# Microcontroller_block.net
KiCad netlist of a schematic drawn in Altium Designer
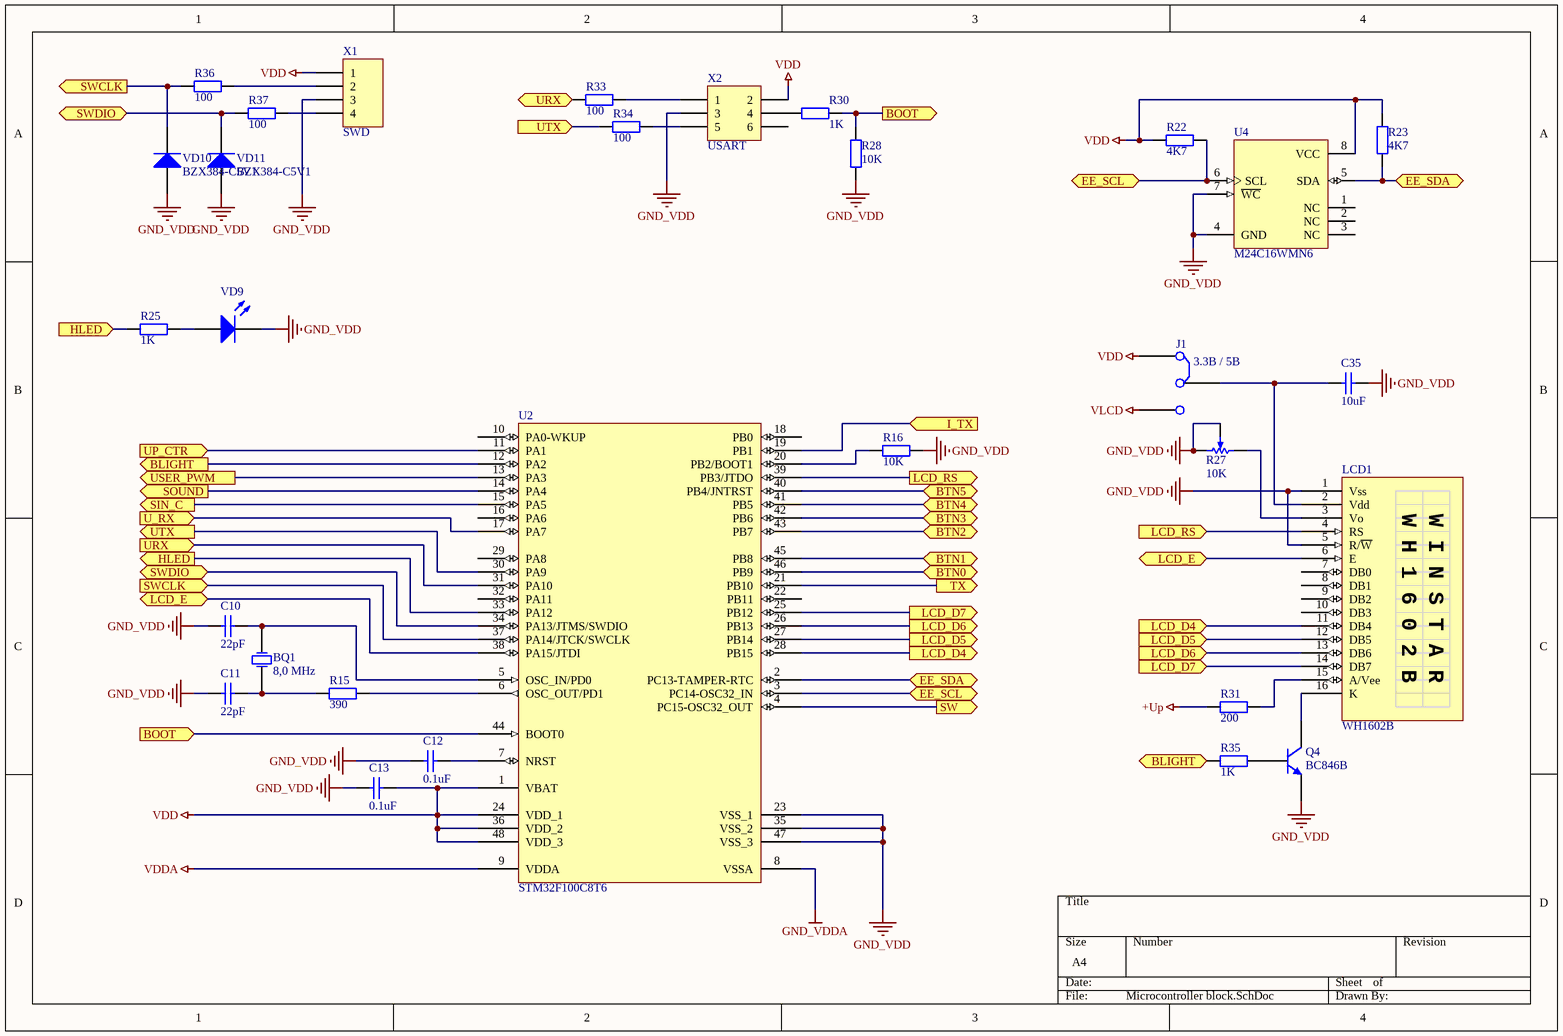
[diagram p0: Microcontroller block.SchDoc]

(export (version "E")
  (design (tool "Eeschema 10.0.6"))
  (components
    (comp (ref "BQ1")
      (value "8,0 MHz")
      (footprint "HC-49/U3H (low profile)")
      (description "Crystal Oscillator")
      (fields (field (name "PUBLISHER") "Altium Limited"))
      (libsource (lib "Quasar ARM") (part "XTAL"))
    )
    (comp (ref "C10")
      (value "22pF")
      (footprint "0805")
      (description "Capacitor")
      (fields (field (name "PUBLISHER") "Altium Limited"))
      (libsource (lib "Quasar ARM") (part "Capacitor SMD"))
    )
    (comp (ref "C11")
      (value "22pF")
      (footprint "0805")
      (description "Capacitor")
      (fields (field (name "PUBLISHER") "Altium Limited"))
      (libsource (lib "Quasar ARM") (part "Capacitor SMD"))
    )
    (comp (ref "C12")
      (value "0.1uF")
      (footprint "0805")
      (description "Capacitor")
      (fields (field (name "PUBLISHER") "Altium Limited"))
      (libsource (lib "Quasar ARM") (part "Capacitor SMD"))
    )
    (comp (ref "C13")
      (value "0.1uF")
      (footprint "1206_SMD_Capacitor")
      (description "Capacitor")
      (fields (field (name "PUBLISHER") "Altium Limited"))
      (libsource (lib "Quasar ARM") (part "Capacitor SMD"))
    )
    (comp (ref "C35")
      (value "10uF")
      (footprint "1206_SMD_Capacitor")
      (description "Capacitor")
      (fields (field (name "PUBLISHER") "Altium Limited"))
      (libsource (lib "Quasar ARM") (part "Capacitor SMD"))
    )
    (comp (ref "J1")
      (value "3.3В / 5В")
      (footprint "1206_SMD_JUMPER SELECTOR")
      (libsource (lib "Quasar ARM") (part "Jump Selector"))
    )
    (comp (ref "LCD1")
      (value "WH1602B")
      (footprint "WS1602B-3")
      (description "Символьный ЖКИ разрешением 16 символов на 2 строки")
      (libsource (lib "Quasar ARM") (part "WH1602B"))
    )
    (comp (ref "Q4")
      (value "BC846B")
      (footprint "SOT23_N")
      (description "NPN General-purpose Transistor")
      (fields (field (name "PUBLISHER") "Altium Limited"))
      (libsource (lib "Quasar ARM") (part "BC846B"))
    )
    (comp (ref "R15")
      (value "390")
      (footprint "1206_SMD_Resistor")
      (description "Resistor")
      (fields (field (name "PUBLISHER") "Altium Limited"))
      (libsource (lib "Quasar ARM") (part "Resistor"))
    )
    (comp (ref "R16")
      (value "10K")
      (footprint "1206_SMD_Resistor")
      (description "Resistor")
      (fields (field (name "PUBLISHER") "Altium Limited"))
      (libsource (lib "Quasar ARM") (part "Resistor"))
    )
    (comp (ref "R22")
      (value "4K7")
      (footprint "1206_SMD_Resistor")
      (description "Resistor")
      (fields (field (name "PUBLISHER") "Altium Limited"))
      (libsource (lib "Quasar ARM") (part "Resistor"))
    )
    (comp (ref "R23")
      (value "4K7")
      (footprint "1206_SMD_Resistor")
      (description "Resistor")
      (fields (field (name "PUBLISHER") "Altium Limited"))
      (libsource (lib "") (part "Resistor_1"))
    )
    (comp (ref "R25")
      (value "1K")
      (footprint "1206_SMD_Resistor")
      (description "Resistor")
      (fields (field (name "PUBLISHER") "Altium Limited"))
      (libsource (lib "") (part "Resistor_2"))
    )
    (comp (ref "R27")
      (value "10K")
      (footprint "3362P")
      (description "Square Trimming Potentiometer")
      (fields (field (name "PUBLISHER") "Altium Limited"))
      (libsource (lib "Quasar ARM") (part "Trimming Potentiometer"))
    )
    (comp (ref "R28")
      (value "10K")
      (footprint "1206_SMD_Resistor")
      (description "Resistor")
      (fields (field (name "PUBLISHER") "Altium Limited"))
      (libsource (lib "") (part "Resistor_1"))
    )
    (comp (ref "R30")
      (value "1K")
      (footprint "1206_SMD_Resistor")
      (description "Resistor")
      (fields (field (name "PUBLISHER") "Altium Limited"))
      (libsource (lib "Quasar ARM") (part "Resistor"))
    )
    (comp (ref "R31")
      (value "200")
      (footprint "1206_SMD_Resistor")
      (description "Resistor")
      (fields (field (name "PUBLISHER") "Altium Limited"))
      (libsource (lib "Quasar ARM") (part "Resistor"))
    )
    (comp (ref "R33")
      (value "100")
      (footprint "1206_SMD_Resistor")
      (description "Resistor")
      (fields (field (name "PUBLISHER") "Altium Limited"))
      (libsource (lib "Quasar ARM") (part "Resistor"))
    )
    (comp (ref "R34")
      (value "100")
      (footprint "1206_SMD_Resistor")
      (description "Resistor")
      (fields (field (name "PUBLISHER") "Altium Limited"))
      (libsource (lib "Quasar ARM") (part "Resistor"))
    )
    (comp (ref "R35")
      (value "1K")
      (footprint "1206_SMD_Resistor")
      (description "Resistor")
      (fields (field (name "PUBLISHER") "Altium Limited"))
      (libsource (lib "Quasar ARM") (part "Resistor"))
    )
    (comp (ref "R36")
      (value "100")
      (footprint "1206_SMD_Resistor")
      (description "Resistor")
      (fields (field (name "PUBLISHER") "Altium Limited"))
      (libsource (lib "Quasar ARM") (part "Resistor"))
    )
    (comp (ref "R37")
      (value "100")
      (footprint "1206_SMD_Resistor")
      (description "Resistor")
      (fields (field (name "PUBLISHER") "Altium Limited"))
      (libsource (lib "Quasar ARM") (part "Resistor"))
    )
    (comp (ref "U2")
      (value "STM32F100C8T6")
      (footprint "LQFP-48_L")
      (description "STM32 ARM-based 32-bit MCU with 64 Kbytes Flash, 48-pin LQFP, Industrial Temperature")
      (fields (field (name "PUBLISHER") "Altium Limited"))
      (libsource (lib "Quasar ARM") (part "STM32F101C8T6"))
    )
    (comp (ref "U4")
      (value "M24C16WMN6")
      (footprint "SO-8")
      (description "16Kbit Serial IІC Bus EEPROM")
      (fields (field (name "PUBLISHER") "Altium Limited"))
      (libsource (lib "Quasar ARM") (part "M24C16WMN6"))
    )
    (comp (ref "VD9")
      (value "LED0")
      (footprint "1206_SMD_Resistor")
      (description "Typical INFRARED GaAs LED")
      (fields (field (name "PUBLISHER") "Altium Limited"))
      (libsource (lib "Quasar ARM") (part "LED0"))
    )
    (comp (ref "VD10")
      (value "BZX384-C5V1")
      (footprint "SOD323")
      (description "Voltage Regulator Diode")
      (fields (field (name "PUBLISHER") "Altium Limited"))
      (libsource (lib "Quasar ARM") (part "BZX84-C5V1"))
    )
    (comp (ref "VD11")
      (value "BZX384-C5V1")
      (footprint "SOD323")
      (description "Voltage Regulator Diode")
      (fields (field (name "PUBLISHER") "Altium Limited"))
      (libsource (lib "Quasar ARM") (part "BZX84-C5V1"))
    )
    (comp (ref "X1")
      (value "SWD")
      (footprint "HDR1X4")
      (description "Header, 4-Pin")
      (fields (field (name "PUBLISHER") "Altium Limited"))
      (libsource (lib "Miscellaneous Connectors") (part "Header 4"))
    )
    (comp (ref "X2")
      (value "USART")
      (footprint "HDR2X3")
      (description "Header, 3-Pin, Dual row")
      (fields (field (name "PUBLISHER") "Altium Limited"))
      (libsource (lib "Miscellaneous Connectors") (part "Header 3X2"))
    )
  )
  (nets
    (net (code "1") (name "+Up") (class "Default")
      (node (ref "R31") (pin "1") (pinfunction "1_1") (pintype "passive"))
    )
    (net (code "2") (name "/BLIGHT") (class "Default")
      (node (ref "R35") (pin "1") (pinfunction "1_1") (pintype "passive"))
      (node (ref "U2") (pin "12") (pinfunction "PA2_12") (pintype "bidirectional"))
    )
    (net (code "3") (name "/BOOT") (class "Default")
      (node (ref "R28") (pin "2") (pinfunction "2_2") (pintype "passive"))
      (node (ref "R30") (pin "2") (pinfunction "2_2") (pintype "passive"))
      (node (ref "U2") (pin "44") (pinfunction "BOOT0_44") (pintype "input"))
    )
    (net (code "4") (name "/BTN0") (class "Default")
      (node (ref "U2") (pin "46") (pinfunction "PB9_46") (pintype "bidirectional"))
    )
    (net (code "5") (name "/BTN1") (class "Default")
      (node (ref "U2") (pin "45") (pinfunction "PB8_45") (pintype "bidirectional"))
    )
    (net (code "6") (name "/BTN2") (class "Default")
      (node (ref "U2") (pin "43") (pinfunction "PB7_43") (pintype "bidirectional"))
    )
    (net (code "7") (name "/BTN3") (class "Default")
      (node (ref "U2") (pin "42") (pinfunction "PB6_42") (pintype "bidirectional"))
    )
    (net (code "8") (name "/BTN4") (class "Default")
      (node (ref "U2") (pin "41") (pinfunction "PB5_41") (pintype "bidirectional"))
    )
    (net (code "9") (name "/BTN5") (class "Default")
      (node (ref "U2") (pin "40") (pinfunction "PB4/JNTRST_40") (pintype "bidirectional"))
    )
    (net (code "10") (name "/EE_SCL") (class "Default")
      (node (ref "R22") (pin "2") (pinfunction "2_2") (pintype "passive"))
      (node (ref "U2") (pin "3") (pinfunction "PC14-OSC32_IN_3") (pintype "bidirectional"))
      (node (ref "U4") (pin "6") (pinfunction "SCL_6") (pintype "input"))
    )
    (net (code "11") (name "/EE_SDA") (class "Default")
      (node (ref "R23") (pin "1") (pinfunction "1_1") (pintype "passive"))
      (node (ref "U2") (pin "2") (pinfunction "PC13-TAMPER-RTC_2") (pintype "bidirectional"))
      (node (ref "U4") (pin "5") (pinfunction "SDA_5") (pintype "bidirectional"))
    )
    (net (code "12") (name "/HLED") (class "Default")
      (node (ref "R25") (pin "2") (pinfunction "2_2") (pintype "passive"))
      (node (ref "U2") (pin "33") (pinfunction "PA12_33") (pintype "bidirectional"))
    )
    (net (code "13") (name "/I_TX") (class "Default")
      (node (ref "U2") (pin "19") (pinfunction "PB1_19") (pintype "bidirectional"))
    )
    (net (code "14") (name "/LCD_D4") (class "Default")
      (node (ref "LCD1") (pin "11") (pinfunction "DB4_11") (pintype "bidirectional"))
      (node (ref "U2") (pin "28") (pinfunction "PB15_28") (pintype "bidirectional"))
    )
    (net (code "15") (name "/LCD_D5") (class "Default")
      (node (ref "LCD1") (pin "12") (pinfunction "DB5_12") (pintype "bidirectional"))
      (node (ref "U2") (pin "27") (pinfunction "PB14_27") (pintype "bidirectional"))
    )
    (net (code "16") (name "/LCD_D6") (class "Default")
      (node (ref "LCD1") (pin "13") (pinfunction "DB6_13") (pintype "bidirectional"))
      (node (ref "U2") (pin "26") (pinfunction "PB13_26") (pintype "bidirectional"))
    )
    (net (code "17") (name "/LCD_D7") (class "Default")
      (node (ref "LCD1") (pin "14") (pinfunction "DB7_14") (pintype "bidirectional"))
      (node (ref "U2") (pin "25") (pinfunction "PB12_25") (pintype "bidirectional"))
    )
    (net (code "18") (name "/LCD_E") (class "Default")
      (node (ref "LCD1") (pin "6") (pinfunction "E_6") (pintype "input"))
      (node (ref "U2") (pin "38") (pinfunction "PA15/JTDI_38") (pintype "bidirectional"))
    )
    (net (code "19") (name "/LCD_RS") (class "Default")
      (node (ref "LCD1") (pin "4") (pinfunction "RS_4") (pintype "input"))
      (node (ref "U2") (pin "39") (pinfunction "PB3/JTDO_39") (pintype "bidirectional"))
    )
    (net (code "20") (name "/SIN_C") (class "Default")
      (node (ref "U2") (pin "15") (pinfunction "PA5_15") (pintype "bidirectional"))
    )
    (net (code "21") (name "/SOUND") (class "Default")
      (node (ref "U2") (pin "14") (pinfunction "PA4_14") (pintype "bidirectional"))
    )
    (net (code "22") (name "/SW") (class "Default")
      (node (ref "U2") (pin "4") (pinfunction "PC15-OSC32_OUT_4") (pintype "bidirectional"))
    )
    (net (code "23") (name "/SWCLK") (class "Default")
      (node (ref "R36") (pin "1") (pinfunction "1_1") (pintype "passive"))
      (node (ref "U2") (pin "37") (pinfunction "PA14/JTCK/SWCLK_37") (pintype "bidirectional"))
      (node (ref "VD10") (pin "3") (pinfunction "K_3") (pintype "passive"))
    )
    (net (code "24") (name "/SWDIO") (class "Default")
      (node (ref "R37") (pin "1") (pinfunction "1_1") (pintype "passive"))
      (node (ref "U2") (pin "34") (pinfunction "PA13/JTMS/SWDIO_34") (pintype "bidirectional"))
      (node (ref "VD11") (pin "3") (pinfunction "K_3") (pintype "passive"))
    )
    (net (code "25") (name "/TX") (class "Default")
      (node (ref "U2") (pin "21") (pinfunction "PB10_21") (pintype "bidirectional"))
    )
    (net (code "26") (name "/UP_CTR") (class "Default")
      (node (ref "U2") (pin "11") (pinfunction "PA1_11") (pintype "bidirectional"))
    )
    (net (code "27") (name "/URX") (class "Default")
      (node (ref "R33") (pin "1") (pinfunction "1_1") (pintype "passive"))
      (node (ref "U2") (pin "31") (pinfunction "PA10_31") (pintype "bidirectional"))
    )
    (net (code "28") (name "/USER_PWM") (class "Default")
      (node (ref "U2") (pin "13") (pinfunction "PA3_13") (pintype "bidirectional"))
    )
    (net (code "29") (name "/UTX") (class "Default")
      (node (ref "R34") (pin "1") (pinfunction "1_1") (pintype "passive"))
      (node (ref "U2") (pin "30") (pinfunction "PA9_30") (pintype "bidirectional"))
    )
    (net (code "30") (name "/U_RX") (class "Default")
      (node (ref "U2") (pin "17") (pinfunction "PA7_17") (pintype "bidirectional"))
    )
    (net (code "31") (name "GND_VDD") (class "Default")
      (node (ref "C10") (pin "1") (pinfunction "1_1") (pintype "passive"))
      (node (ref "C11") (pin "1") (pinfunction "1_1") (pintype "passive"))
      (node (ref "C12") (pin "1") (pinfunction "1_1") (pintype "passive"))
      (node (ref "C13") (pin "1") (pinfunction "1_1") (pintype "passive"))
      (node (ref "C35") (pin "2") (pinfunction "2_2") (pintype "passive"))
      (node (ref "LCD1") (pin "1") (pinfunction "Vss_1") (pintype "power_in"))
      (node (ref "LCD1") (pin "5") (pinfunction "R/~{W}_5") (pintype "input"))
      (node (ref "Q4") (pin "2") (pinfunction "E_2") (pintype "passive"))
      (node (ref "R16") (pin "2") (pinfunction "2_2") (pintype "passive"))
      (node (ref "R27") (pin "1") (pinfunction "1_1") (pintype "passive"))
      (node (ref "R27") (pin "2") (pinfunction "2_2") (pintype "passive"))
      (node (ref "R28") (pin "1") (pinfunction "1_1") (pintype "passive"))
      (node (ref "U2") (pin "23") (pinfunction "VSS_1_23") (pintype "power_in"))
      (node (ref "U2") (pin "35") (pinfunction "VSS_2_35") (pintype "power_in"))
      (node (ref "U2") (pin "47") (pinfunction "VSS_3_47") (pintype "power_in"))
      (node (ref "U4") (pin "4") (pinfunction "GND_4") (pintype "power_in"))
      (node (ref "U4") (pin "7") (pinfunction "~{WC}_7") (pintype "input"))
      (node (ref "VD10") (pin "1") (pinfunction "A_1") (pintype "passive"))
      (node (ref "VD11") (pin "1") (pinfunction "A_1") (pintype "passive"))
      (node (ref "VD9") (pin "2") (pinfunction "K_2") (pintype "passive"))
      (node (ref "X1") (pin "3") (pinfunction "3_3") (pintype "passive"))
      (node (ref "X2") (pin "3") (pinfunction "3_3") (pintype "passive"))
    )
    (net (code "32") (name "GND_VDDA") (class "Default")
      (node (ref "U2") (pin "8") (pinfunction "VSSA_8") (pintype "power_in"))
    )
    (net (code "33") (name "Net-(BQ1-OSC1)") (class "Default")
      (node (ref "BQ1") (pin "1") (pinfunction "OSC1_1") (pintype "passive"))
      (node (ref "C11") (pin "2") (pinfunction "2_2") (pintype "passive"))
      (node (ref "R15") (pin "1") (pinfunction "1_1") (pintype "passive"))
    )
    (net (code "34") (name "Net-(BQ1-OSC2)") (class "Default")
      (node (ref "BQ1") (pin "2") (pinfunction "OSC2_2") (pintype "passive"))
      (node (ref "C10") (pin "2") (pinfunction "2_2") (pintype "passive"))
      (node (ref "U2") (pin "5") (pinfunction "OSC_IN/PD0_5") (pintype "input"))
    )
    (net (code "35") (name "Net-(LCD1-A{slash}Vee)") (class "Default")
      (node (ref "LCD1") (pin "15") (pinfunction "A/Vee_15") (pintype "bidirectional"))
      (node (ref "R31") (pin "2") (pinfunction "2_2") (pintype "passive"))
    )
    (net (code "36") (name "Net-(LCD1-K)") (class "Default")
      (node (ref "LCD1") (pin "16") (pinfunction "K_16") (pintype "power_in"))
      (node (ref "Q4") (pin "3") (pinfunction "C_3") (pintype "passive"))
    )
    (net (code "37") (name "Net-(LCD1-Vdd)") (class "Default")
      (node (ref "C35") (pin "1") (pinfunction "1_1") (pintype "passive"))
      (node (ref "J1") (pin "0") (pinfunction "0_0") (pintype "passive"))
      (node (ref "LCD1") (pin "2") (pinfunction "Vdd_2") (pintype "power_in"))
    )
    (net (code "38") (name "Net-(LCD1-Vo)") (class "Default")
      (node (ref "LCD1") (pin "3") (pinfunction "Vo_3") (pintype "power_in"))
      (node (ref "R27") (pin "3") (pinfunction "3_3") (pintype "passive"))
    )
    (net (code "39") (name "Net-(Q4-B)") (class "Default")
      (node (ref "Q4") (pin "1") (pinfunction "B_1") (pintype "passive"))
      (node (ref "R35") (pin "2") (pinfunction "2_2") (pintype "passive"))
    )
    (net (code "40") (name "Net-(R30-Pad1)") (class "Default")
      (node (ref "R30") (pin "1") (pinfunction "1_1") (pintype "passive"))
      (node (ref "X2") (pin "4") (pinfunction "4_4") (pintype "passive"))
    )
    (net (code "41") (name "Net-(R33-Pad2)") (class "Default")
      (node (ref "R33") (pin "2") (pinfunction "2_2") (pintype "passive"))
      (node (ref "X2") (pin "1") (pinfunction "1_1") (pintype "passive"))
    )
    (net (code "42") (name "Net-(R34-Pad2)") (class "Default")
      (node (ref "R34") (pin "2") (pinfunction "2_2") (pintype "passive"))
      (node (ref "X2") (pin "5") (pinfunction "5_5") (pintype "passive"))
    )
    (net (code "43") (name "Net-(R36-Pad2)") (class "Default")
      (node (ref "R36") (pin "2") (pinfunction "2_2") (pintype "passive"))
      (node (ref "X1") (pin "2") (pinfunction "2_2") (pintype "passive"))
    )
    (net (code "44") (name "Net-(R37-Pad2)") (class "Default")
      (node (ref "R37") (pin "2") (pinfunction "2_2") (pintype "passive"))
      (node (ref "X1") (pin "4") (pinfunction "4_4") (pintype "passive"))
    )
    (net (code "45") (name "Net-(U2-NRST)") (class "Default")
      (node (ref "C12") (pin "2") (pinfunction "2_2") (pintype "passive"))
      (node (ref "U2") (pin "7") (pinfunction "NRST_7") (pintype "bidirectional"))
    )
    (net (code "46") (name "Net-(U2-OSC_OUT{slash}PD1)") (class "Default")
      (node (ref "R15") (pin "2") (pinfunction "2_2") (pintype "passive"))
      (node (ref "U2") (pin "6") (pinfunction "OSC_OUT/PD1_6") (pintype "output"))
    )
    (net (code "47") (name "Net-(U2-PB2{slash}BOOT1)") (class "Default")
      (node (ref "R16") (pin "1") (pinfunction "1_1") (pintype "passive"))
      (node (ref "U2") (pin "20") (pinfunction "PB2/BOOT1_20") (pintype "bidirectional"))
    )
    (net (code "48") (name "Net-(VD9-A)") (class "Default")
      (node (ref "R25") (pin "1") (pinfunction "1_1") (pintype "passive"))
      (node (ref "VD9") (pin "1") (pinfunction "A_1") (pintype "passive"))
    )
    (net (code "49") (name "VDD") (class "Default")
      (node (ref "C13") (pin "2") (pinfunction "2_2") (pintype "passive"))
      (node (ref "J1") (pin "1") (pinfunction "1_1") (pintype "passive"))
      (node (ref "R22") (pin "1") (pinfunction "1_1") (pintype "passive"))
      (node (ref "R23") (pin "2") (pinfunction "2_2") (pintype "passive"))
      (node (ref "U2") (pin "1") (pinfunction "VBAT_1") (pintype "power_in"))
      (node (ref "U2") (pin "24") (pinfunction "VDD_1_24") (pintype "power_in"))
      (node (ref "U2") (pin "36") (pinfunction "VDD_2_36") (pintype "power_in"))
      (node (ref "U2") (pin "48") (pinfunction "VDD_3_48") (pintype "power_in"))
      (node (ref "U4") (pin "8") (pinfunction "VCC_8") (pintype "power_in"))
      (node (ref "X1") (pin "1") (pinfunction "1_1") (pintype "passive"))
      (node (ref "X2") (pin "2") (pinfunction "2_2") (pintype "passive"))
    )
    (net (code "50") (name "VDDA") (class "Default")
      (node (ref "U2") (pin "9") (pinfunction "VDDA_9") (pintype "power_in"))
    )
    (net (code "51") (name "VLCD") (class "Default")
      (node (ref "J1") (pin "2") (pinfunction "2_2") (pintype "passive"))
    )
    (net (code "52") (name "unconnected-(LCD1-DB0-Pad7)") (class "Default")
      (node (ref "LCD1") (pin "7") (pinfunction "DB0_7") (pintype "bidirectional"))
    )
    (net (code "53") (name "unconnected-(LCD1-DB1-Pad8)") (class "Default")
      (node (ref "LCD1") (pin "8") (pinfunction "DB1_8") (pintype "bidirectional"))
    )
    (net (code "54") (name "unconnected-(LCD1-DB2-Pad9)") (class "Default")
      (node (ref "LCD1") (pin "9") (pinfunction "DB2_9") (pintype "bidirectional"))
    )
    (net (code "55") (name "unconnected-(LCD1-DB3-Pad10)") (class "Default")
      (node (ref "LCD1") (pin "10") (pinfunction "DB3_10") (pintype "bidirectional"))
    )
    (net (code "56") (name "unconnected-(U2-PA0-WKUP-Pad10)") (class "Default")
      (node (ref "U2") (pin "10") (pinfunction "PA0-WKUP_10") (pintype "bidirectional"))
    )
    (net (code "57") (name "unconnected-(U2-PA6-Pad16)") (class "Default")
      (node (ref "U2") (pin "16") (pinfunction "PA6_16") (pintype "bidirectional"))
    )
    (net (code "58") (name "unconnected-(U2-PA8-Pad29)") (class "Default")
      (node (ref "U2") (pin "29") (pinfunction "PA8_29") (pintype "bidirectional"))
    )
    (net (code "59") (name "unconnected-(U2-PA11-Pad32)") (class "Default")
      (node (ref "U2") (pin "32") (pinfunction "PA11_32") (pintype "bidirectional"))
    )
    (net (code "60") (name "unconnected-(U2-PB0-Pad18)") (class "Default")
      (node (ref "U2") (pin "18") (pinfunction "PB0_18") (pintype "bidirectional"))
    )
    (net (code "61") (name "unconnected-(U2-PB11-Pad22)") (class "Default")
      (node (ref "U2") (pin "22") (pinfunction "PB11_22") (pintype "bidirectional"))
    )
    (net (code "62") (name "unconnected-(U4-NC-Pad1)") (class "Default")
      (node (ref "U4") (pin "1") (pinfunction "NC_1") (pintype "passive"))
    )
    (net (code "63") (name "unconnected-(U4-NC-Pad2)") (class "Default")
      (node (ref "U4") (pin "2") (pinfunction "NC_2") (pintype "passive"))
    )
    (net (code "64") (name "unconnected-(U4-NC-Pad3)") (class "Default")
      (node (ref "U4") (pin "3") (pinfunction "NC_3") (pintype "passive"))
    )
    (net (code "65") (name "unconnected-(X2-Pad6)") (class "Default")
      (node (ref "X2") (pin "6") (pinfunction "6_6") (pintype "passive"))
    )
  )
)
